# 3_3V_to_VADJ.net
KiCad netlist of a schematic drawn in Altium Designer
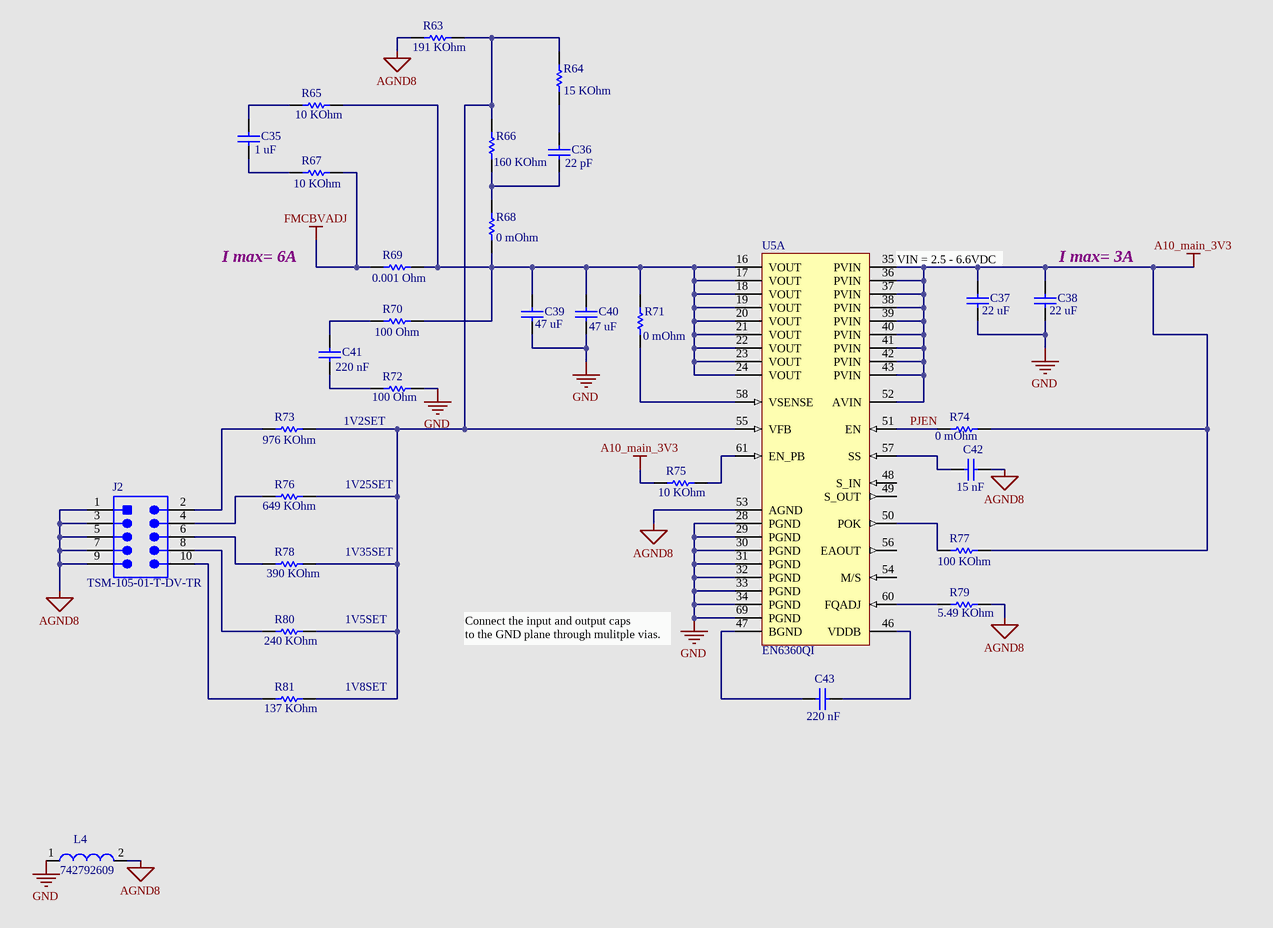
[diagram p0: 3.3V_to_VADJ.SchDoc]

(export (version "E")
  (design (tool "Eeschema 10.0.6"))
  (components
    (comp (ref "C35")
      (value "CGB2A1X5R1E105K033BC")
      (footprint "CAPC1005X33X10LL5")
      (description "Chip Capacitor, 1 uF, +/- 10%, 25 V, -55 to 85 degC, 0402 (1005 Metric), RoHS, Tape and Reel")
      (fields (field (name "TOLERANCE") "10%") (field (name "CAPACITANCE") "1 uF"))
      (libsource (lib "Altium Content Vault") (part "CAP-NP-2"))
    )
    (comp (ref "C36")
      (value "C1005C0G1H220J050BA")
      (footprint "CAPC1005X55X10LL05")
      (description "Chip Capacitor, 22 pF, +/- 5%, 50 V, -55 to 125 degC, 0402 (1005 Metric), RoHS, Tape and Reel")
      (fields (field (name "TOLERANCE") "5%") (field (name "CAPACITANCE") "22 pF"))
      (libsource (lib "") (part "CAP-NP-2_1"))
    )
    (comp (ref "C37")
      (value "GRM31CR61E226KE15L")
      (footprint "CAPC3216X180X55ML20T25")
      (description "Chip Capacitor, 22 uF, +/- 10%, 25 V, -55 to 85 degC, 1206 (3216 Metric), RoHS, Tape and Reel")
      (fields (field (name "TOLERANCE") "10%") (field (name "CAPACITANCE") "22 uF"))
      (libsource (lib "") (part "CAP-NP-2_1"))
    )
    (comp (ref "C38")
      (value "GRM31CR61E226KE15L")
      (footprint "CAPC3216X180X55ML20T25")
      (description "Chip Capacitor, 22 uF, +/- 10%, 25 V, -55 to 85 degC, 1206 (3216 Metric), RoHS, Tape and Reel")
      (fields (field (name "TOLERANCE") "10%") (field (name "CAPACITANCE") "22 uF"))
      (libsource (lib "") (part "CAP-NP-2_1"))
    )
    (comp (ref "C39")
      (value "C3216X5R1A476M160AB")
      (footprint "CAPC3216X180X20ML20")
      (description "Chip Capacitor, 47 uF, +/- 20%, 10 V, -55 to 85 degC, 1206 (3216 Metric), RoHS, Tape and Reel")
      (fields (field (name "TOLERANCE") "20%") (field (name "CAPACITANCE") "47 uF"))
      (libsource (lib "Altium Content Vault") (part "CAP-NP-2"))
    )
    (comp (ref "C40")
      (value "C3216X5R1A476M160AB")
      (footprint "CAPC3216X180X20ML20")
      (description "Chip Capacitor, 47 uF, +/- 20%, 10 V, -55 to 85 degC, 1206 (3216 Metric), RoHS, Tape and Reel")
      (fields (field (name "TOLERANCE") "20%") (field (name "CAPACITANCE") "47 uF"))
      (libsource (lib "Altium Content Vault") (part "CAP-NP-2"))
    )
    (comp (ref "C41")
      (value "GRM155R61A224KE19D")
      (footprint "CAPC1005X55X25NL05T10")
      (description "Chip Capacitor, 220 nF, +/- 10%, 10 V, -55 to 85 degC, 0402 (1005 Metric), RoHS, Tape and Reel")
      (fields
        (field (name "TOLERANCE") "10%")
        (field (name "CAPACITANCE") "220 nF")
        (field (name "MANUFACTURER") "Basic Passives")
      )
      (libsource (lib "") (part "CAP-NP-2_1"))
    )
    (comp (ref "C42")
      (value "VJ0402Y153JXQPW1BC")
      (footprint "CAPC1005X55X23ML05T8")
      (description "Chip Capacitor, 15 nF, +/- 5%, 10 V, -55 to 125 degC, 0402 (1005 Metric), RoHS, Tape and Reel")
      (fields (field (name "CAPACITANCE") "15 nF") (field (name "TOLERANCE") "5%"))
      (libsource (lib "") (part "CAP-NP-2_1"))
    )
    (comp (ref "C43")
      (value "GRM155R61A224KE19D")
      (footprint "CAPC1005X55X25NL05T10")
      (description "Chip Capacitor, 220 nF, +/- 10%, 10 V, -55 to 85 degC, 0402 (1005 Metric), RoHS, Tape and Reel")
      (fields
        (field (name "TOLERANCE") "10%")
        (field (name "CAPACITANCE") "220 nF")
        (field (name "MANUFACTURER") "Basic Passives")
      )
      (libsource (lib "") (part "CAP-NP-2_1"))
    )
    (comp (ref "J2")
      (value "TSM-105-01-T-DV-TR")
      (footprint "SMTC-TSM-105-01-T-DV_V")
      (description "Male Header, Pitch 2.54 mm, 2 x 5 Position, Height 9.65 mm, -55 to 105 degC, RoHS, Tape and Reel")
      (fields (field (name "MANUFACTURER") "Samtec"))
      (libsource (lib "Altium Content Vault") (part "CMP-1707-00003-1"))
    )
    (comp (ref "L4")
      (value "742792609")
      (footprint "SMD-0603")
      (description "SMD EMI Suppression Ferrite Bead WE-CBF, Z = 30 Ohm")
      (libsource (lib "Altium Content Vault") (part "CMP-0220-00193-1"))
    )
    (comp (ref "R63")
      (value "CRCW0402191KFKED")
      (footprint "RESC1005X40X25LL05T05")
      (description "Chip Resistor, 191 KOhm, +/- 1%, 63 mW, -55 to 155 degC, 0402 (1005 Metric), RoHS, Tape and Reel")
      (fields
        (field (name "TOLERANCE") "1%")
        (field (name "RESISTANCE") "191 KOhm")
        (field (name "MANUFACTURER") "Basic Passives")
      )
      (libsource (lib "Altium Content Vault") (part "RES-2"))
    )
    (comp (ref "R64")
      (value "ERJ-2RKF1502X")
      (footprint "RESC1005X40X25ML05T05")
      (description "Chip Resistor, 15 KOhm, +/- 1%, 100 mW, -55 to 155 degC, 0402 (1005 Metric), RoHS, Tape and Reel")
      (fields
        (field (name "RESISTANCE") "15 KOhm")
        (field (name "TOLERANCE") "1%")
        (field (name "MANUFACTURER") "Basic Passives")
      )
      (libsource (lib "Altium Content Vault") (part "RES-2"))
    )
    (comp (ref "R65")
      (value "ERJ-2RKF1002X")
      (footprint "RESC1005X40X25NL05T05")
      (description "Chip Resistor, 10 KOhm, +/- 1%, 100 mW, -55 to 155 degC, 0402 (1005 Metric), RoHS, Tape and Reel")
      (fields
        (field (name "TOLERANCE") "1%")
        (field (name "RESISTANCE") "10 KOhm")
        (field (name "MANUFACTURER") "Basic Passives")
      )
      (libsource (lib "Altium Content Vault") (part "RES-2"))
    )
    (comp (ref "R66")
      (value "CRCW0402160KFKED")
      (footprint "RESC1005X40X25ML05T05")
      (description "Chip Resistor, 160 KOhm, +/- 1%, 63 mW, -55 to 155 degC, 0402 (1005 Metric), RoHS, Tape and Reel")
      (fields
        (field (name "TOLERANCE") "1%")
        (field (name "RESISTANCE") "160 KOhm")
        (field (name "MANUFACTURER") "Basic Passives")
      )
      (libsource (lib "Altium Content Vault") (part "RES-2"))
    )
    (comp (ref "R67")
      (value "ERJ-2RKF1002X")
      (footprint "RESC1005X40X25NL05T05")
      (description "Chip Resistor, 10 KOhm, +/- 1%, 100 mW, -55 to 155 degC, 0402 (1005 Metric), RoHS, Tape and Reel")
      (fields
        (field (name "TOLERANCE") "1%")
        (field (name "RESISTANCE") "10 KOhm")
        (field (name "MANUFACTURER") "Basic Passives")
      )
      (libsource (lib "Altium Content Vault") (part "RES-2"))
    )
    (comp (ref "R68")
      (value "ERJ-2GE0R00X")
      (footprint "RESC1005X40X25ML05T05")
      (description "Chip Resistor, 0 mOhm, +/- 5%, 100 mW, -55 to 155 degC, 0402 (1005 Metric), RoHS, Tape and Reel")
      (fields
        (field (name "TOLERANCE") "5%")
        (field (name "RESISTANCE") "0 mOhm")
        (field (name "MANUFACTURER") "Basic Passives")
      )
      (libsource (lib "Altium Content Vault") (part "RES-2"))
    )
    (comp (ref "R69")
      (value "WSLP12061L000FEA")
      (footprint "RESC3216X89X104LL25T25")
      (description "Chip Resistor, 0.001 Ohm, +/- 1%, 1 W, -65 to 170 degC, 1206 (3216 Metric), RoHS, Tape and Reel")
      (fields (field (name "TOLERANCE") "1%") (field (name "RESISTANCE") "0.001 Ohm"))
      (libsource (lib "Altium Content Vault") (part "RES-2"))
    )
    (comp (ref "R70")
      (value "ERJ-2RKF1000X")
      (footprint "RESC1005X40X25LL05T05")
      (description "Chip Resistor, 100 Ohm, +/- 1%, 100 mW, -55 to 155 degC, 0402 (1005 Metric), RoHS, Tape and Reel")
      (fields
        (field (name "TOLERANCE") "1%")
        (field (name "RESISTANCE") "100 Ohm")
        (field (name "MANUFACTURER") "Basic Passives")
      )
      (libsource (lib "Altium Content Vault") (part "RES-2"))
    )
    (comp (ref "R71")
      (value "ERJ-2GE0R00X")
      (footprint "RESC1005X40X25ML05T05")
      (description "Chip Resistor, 0 mOhm, +/- 5%, 100 mW, -55 to 155 degC, 0402 (1005 Metric), RoHS, Tape and Reel")
      (fields
        (field (name "TOLERANCE") "5%")
        (field (name "RESISTANCE") "0 mOhm")
        (field (name "MANUFACTURER") "Basic Passives")
      )
      (libsource (lib "Altium Content Vault") (part "RES-2"))
    )
    (comp (ref "R72")
      (value "ERJ-2RKF1000X")
      (footprint "RESC1005X40X25LL05T05")
      (description "Chip Resistor, 100 Ohm, +/- 1%, 100 mW, -55 to 155 degC, 0402 (1005 Metric), RoHS, Tape and Reel")
      (fields
        (field (name "TOLERANCE") "1%")
        (field (name "RESISTANCE") "100 Ohm")
        (field (name "MANUFACTURER") "Basic Passives")
      )
      (libsource (lib "Altium Content Vault") (part "RES-2"))
    )
    (comp (ref "R73")
      (value "CRCW0402976KFKED")
      (footprint "RESC1005X40X25ML05T05")
      (description "Chip Resistor, 976 KOhm, +/- 1%, 63 mW, -55 to 155 degC, 0402 (1005 Metric), RoHS, Tape and Reel")
      (fields
        (field (name "RESISTANCE") "976 KOhm")
        (field (name "TOLERANCE") "1%")
        (field (name "MANUFACTURER") "Basic Passives")
      )
      (libsource (lib "Altium Content Vault") (part "RES-2"))
    )
    (comp (ref "R74")
      (value "ERJ-2GE0R00X")
      (footprint "RESC1005X40X25ML05T05")
      (description "Chip Resistor, 0 mOhm, +/- 5%, 100 mW, -55 to 155 degC, 0402 (1005 Metric), RoHS, Tape and Reel")
      (fields
        (field (name "TOLERANCE") "5%")
        (field (name "RESISTANCE") "0 mOhm")
        (field (name "MANUFACTURER") "Basic Passives")
      )
      (libsource (lib "Altium Content Vault") (part "RES-2"))
    )
    (comp (ref "R75")
      (value "ERJ-2RKF1002X")
      (footprint "RESC1005X40X25NL05T05")
      (description "Chip Resistor, 10 KOhm, +/- 1%, 100 mW, -55 to 155 degC, 0402 (1005 Metric), RoHS, Tape and Reel")
      (fields
        (field (name "TOLERANCE") "1%")
        (field (name "RESISTANCE") "10 KOhm")
        (field (name "MANUFACTURER") "Basic Passives")
      )
      (libsource (lib "Altium Content Vault") (part "RES-2"))
    )
    (comp (ref "R76")
      (value "CRCW0402649KFKED")
      (footprint "RESC1005X40X25LL05T05")
      (description "Chip Resistor, 649 KOhm, +/- 1%, 63 mW, -55 to 155 degC, 0402 (1005 Metric), RoHS, Tape and Reel")
      (fields
        (field (name "RESISTANCE") "649 KOhm")
        (field (name "TOLERANCE") "1%")
        (field (name "MANUFACTURER") "Basic Passives")
      )
      (libsource (lib "Altium Content Vault") (part "RES-2"))
    )
    (comp (ref "R77")
      (value "ERJ-2RKF1003X")
      (footprint "RESC1005X40X25LL05T05")
      (description "Chip Resistor, 100 KOhm, +/- 1%, 100 mW, -55 to 155 degC, 0402 (1005 Metric), RoHS, Tape and Reel")
      (fields
        (field (name "RESISTANCE") "100 KOhm")
        (field (name "TOLERANCE") "1%")
        (field (name "MANUFACTURER") "Basic Passives")
      )
      (libsource (lib "Altium Content Vault") (part "RES-2"))
    )
    (comp (ref "R78")
      (value "CRCW0402390KFKED")
      (footprint "RESC1005X40X25LL05T05")
      (description "Chip Resistor, 390 KOhm, +/- 1%, 63 mW, -55 to 155 degC, 0402 (1005 Metric), RoHS, Tape and Reel")
      (fields
        (field (name "RESISTANCE") "390 KOhm")
        (field (name "TOLERANCE") "1%")
        (field (name "MANUFACTURER") "Basic Passives")
      )
      (libsource (lib "Altium Content Vault") (part "RES-2"))
    )
    (comp (ref "R79")
      (value "ERJ-2RKF5491X")
      (footprint "RESC1005X40X25NL05T05")
      (description "Chip Resistor, 5.49 KOhm, +/- 1%, 100 mW, -55 to 155 degC, 0402 (1005 Metric), RoHS, Tape and Reel")
      (fields
        (field (name "TOLERANCE") "1%")
        (field (name "RESISTANCE") "5.49 KOhm")
        (field (name "MANUFACTURER") "Basic Passives")
      )
      (libsource (lib "Altium Content Vault") (part "RES-2"))
    )
    (comp (ref "R80")
      (value "ERJ-2RKF2403X")
      (footprint "RESC1005X40X25NL05T05")
      (description "Chip Resistor, 240 KOhm, +/- 1%, 100 mW, -55 to 155 degC, 0402 (1005 Metric), RoHS, Tape and Reel")
      (fields
        (field (name "RESISTANCE") "240 KOhm")
        (field (name "TOLERANCE") "1%")
        (field (name "MANUFACTURER") "Basic Passives")
      )
      (libsource (lib "Altium Content Vault") (part "RES-2"))
    )
    (comp (ref "R81")
      (value "CRCW0402137KFKED")
      (footprint "RESC1005X40X25LL05T05")
      (description "Chip Resistor, 137 KOhm, +/- 1%, 63 mW, -55 to 155 degC, 0402 (1005 Metric), RoHS, Tape and Reel")
      (fields
        (field (name "RESISTANCE") "137 KOhm")
        (field (name "TOLERANCE") "1%")
        (field (name "MANUFACTURER") "Basic Passives")
      )
      (libsource (lib "Altium Content Vault") (part "RES-2"))
    )
    (comp (ref "U5")
      (value "EN6360QI")
      (footprint "ALTR-QFN-68_A-305_V")
      (libsource (lib "Altium Content Vault") (part "ALTR-EN6360QI-QFN68"))
    )
  )
  (nets
    (net (code "1") (name "/PJEN") (class "Default")
      (node (ref "R74") (pin "1") (pinfunction "1_1") (pintype "passive"))
      (node (ref "U5") (pin "51") (pinfunction "EN_51") (pintype "input"))
    )
    (net (code "2") (name "A10_main_3V3") (class "Default")
      (node (ref "C37") (pin "2") (pinfunction "2_2") (pintype "passive"))
      (node (ref "C38") (pin "2") (pinfunction "2_2") (pintype "passive"))
      (node (ref "R74") (pin "2") (pinfunction "2_2") (pintype "passive"))
      (node (ref "R75") (pin "1") (pinfunction "1_1") (pintype "passive"))
      (node (ref "R77") (pin "2") (pinfunction "2_2") (pintype "passive"))
      (node (ref "U5") (pin "35") (pinfunction "PVIN_35") (pintype "power_in"))
      (node (ref "U5") (pin "36") (pinfunction "PVIN_36") (pintype "power_in"))
      (node (ref "U5") (pin "37") (pinfunction "PVIN_37") (pintype "power_in"))
      (node (ref "U5") (pin "38") (pinfunction "PVIN_38") (pintype "power_in"))
      (node (ref "U5") (pin "39") (pinfunction "PVIN_39") (pintype "power_in"))
      (node (ref "U5") (pin "40") (pinfunction "PVIN_40") (pintype "power_in"))
      (node (ref "U5") (pin "41") (pinfunction "PVIN_41") (pintype "power_in"))
      (node (ref "U5") (pin "42") (pinfunction "PVIN_42") (pintype "power_in"))
      (node (ref "U5") (pin "43") (pinfunction "PVIN_43") (pintype "power_in"))
      (node (ref "U5") (pin "52") (pinfunction "AVIN_52") (pintype "power_in"))
    )
    (net (code "3") (name "AGND8") (class "Default")
      (node (ref "C42") (pin "1") (pinfunction "1_1") (pintype "passive"))
      (node (ref "J2") (pin "1") (pinfunction "1_1") (pintype "passive"))
      (node (ref "J2") (pin "3") (pinfunction "3_3") (pintype "passive"))
      (node (ref "J2") (pin "5") (pinfunction "5_5") (pintype "passive"))
      (node (ref "J2") (pin "7") (pinfunction "7_7") (pintype "passive"))
      (node (ref "J2") (pin "9") (pinfunction "9_9") (pintype "passive"))
      (node (ref "L4") (pin "2") (pinfunction "2_2") (pintype "passive"))
      (node (ref "R63") (pin "1") (pinfunction "1_1") (pintype "passive"))
      (node (ref "R79") (pin "2") (pinfunction "2_2") (pintype "passive"))
      (node (ref "U5") (pin "53") (pinfunction "AGND_53") (pintype "power_in"))
    )
    (net (code "4") (name "FMCBVADJ") (class "Default")
      (node (ref "R67") (pin "2") (pinfunction "2_2") (pintype "passive"))
      (node (ref "R69") (pin "1") (pinfunction "1_1") (pintype "passive"))
    )
    (net (code "5") (name "GND") (class "Default")
      (node (ref "C37") (pin "1") (pinfunction "1_1") (pintype "passive"))
      (node (ref "C38") (pin "1") (pinfunction "1_1") (pintype "passive"))
      (node (ref "C39") (pin "1") (pinfunction "1_1") (pintype "passive"))
      (node (ref "C40") (pin "1") (pinfunction "1_1") (pintype "passive"))
      (node (ref "L4") (pin "1") (pinfunction "1_1") (pintype "passive"))
      (node (ref "R72") (pin "1") (pinfunction "1_1") (pintype "passive"))
      (node (ref "U5") (pin "28") (pinfunction "PGND_28") (pintype "power_in"))
      (node (ref "U5") (pin "29") (pinfunction "PGND_29") (pintype "power_in"))
      (node (ref "U5") (pin "30") (pinfunction "PGND_30") (pintype "power_in"))
      (node (ref "U5") (pin "31") (pinfunction "PGND_31") (pintype "power_in"))
      (node (ref "U5") (pin "32") (pinfunction "PGND_32") (pintype "power_in"))
      (node (ref "U5") (pin "33") (pinfunction "PGND_33") (pintype "power_in"))
      (node (ref "U5") (pin "34") (pinfunction "PGND_34") (pintype "power_in"))
      (node (ref "U5") (pin "69") (pinfunction "PGND_69") (pintype "power_in"))
    )
    (net (code "6") (name "Net-(C35-Pad1)") (class "Default")
      (node (ref "C35") (pin "1") (pinfunction "1_1") (pintype "passive"))
      (node (ref "R67") (pin "1") (pinfunction "1_1") (pintype "passive"))
    )
    (net (code "7") (name "Net-(C35-Pad2)") (class "Default")
      (node (ref "C35") (pin "2") (pinfunction "2_2") (pintype "passive"))
      (node (ref "R65") (pin "1") (pinfunction "1_1") (pintype "passive"))
    )
    (net (code "8") (name "Net-(C36-Pad1)") (class "Default")
      (node (ref "C36") (pin "1") (pinfunction "1_1") (pintype "passive"))
      (node (ref "R66") (pin "1") (pinfunction "1_1") (pintype "passive"))
      (node (ref "R68") (pin "2") (pinfunction "2_2") (pintype "passive"))
    )
    (net (code "9") (name "Net-(C36-Pad2)") (class "Default")
      (node (ref "C36") (pin "2") (pinfunction "2_2") (pintype "passive"))
      (node (ref "R64") (pin "1") (pinfunction "1_1") (pintype "passive"))
    )
    (net (code "10") (name "Net-(C39-Pad2)") (class "Default")
      (node (ref "C39") (pin "2") (pinfunction "2_2") (pintype "passive"))
      (node (ref "C40") (pin "2") (pinfunction "2_2") (pintype "passive"))
      (node (ref "R65") (pin "2") (pinfunction "2_2") (pintype "passive"))
      (node (ref "R68") (pin "1") (pinfunction "1_1") (pintype "passive"))
      (node (ref "R69") (pin "2") (pinfunction "2_2") (pintype "passive"))
      (node (ref "R70") (pin "1") (pinfunction "1_1") (pintype "passive"))
      (node (ref "R71") (pin "2") (pinfunction "2_2") (pintype "passive"))
      (node (ref "U5") (pin "16") (pinfunction "VOUT_16") (pintype "power_in"))
      (node (ref "U5") (pin "17") (pinfunction "VOUT_17") (pintype "power_in"))
      (node (ref "U5") (pin "18") (pinfunction "VOUT_18") (pintype "power_in"))
      (node (ref "U5") (pin "19") (pinfunction "VOUT_19") (pintype "power_in"))
      (node (ref "U5") (pin "20") (pinfunction "VOUT_20") (pintype "power_in"))
      (node (ref "U5") (pin "21") (pinfunction "VOUT_21") (pintype "power_in"))
      (node (ref "U5") (pin "22") (pinfunction "VOUT_22") (pintype "power_in"))
      (node (ref "U5") (pin "23") (pinfunction "VOUT_23") (pintype "power_in"))
      (node (ref "U5") (pin "24") (pinfunction "VOUT_24") (pintype "power_in"))
    )
    (net (code "11") (name "Net-(C41-Pad1)") (class "Default")
      (node (ref "C41") (pin "1") (pinfunction "1_1") (pintype "passive"))
      (node (ref "R70") (pin "2") (pinfunction "2_2") (pintype "passive"))
    )
    (net (code "12") (name "Net-(C41-Pad2)") (class "Default")
      (node (ref "C41") (pin "2") (pinfunction "2_2") (pintype "passive"))
      (node (ref "R72") (pin "2") (pinfunction "2_2") (pintype "passive"))
    )
    (net (code "13") (name "Net-(J2-Pad2)") (class "Default")
      (node (ref "J2") (pin "2") (pinfunction "2_2") (pintype "passive"))
      (node (ref "R73") (pin "1") (pinfunction "1_1") (pintype "passive"))
    )
    (net (code "14") (name "Net-(J2-Pad4)") (class "Default")
      (node (ref "J2") (pin "4") (pinfunction "4_4") (pintype "passive"))
      (node (ref "R76") (pin "1") (pinfunction "1_1") (pintype "passive"))
    )
    (net (code "15") (name "Net-(J2-Pad6)") (class "Default")
      (node (ref "J2") (pin "6") (pinfunction "6_6") (pintype "passive"))
      (node (ref "R78") (pin "1") (pinfunction "1_1") (pintype "passive"))
    )
    (net (code "16") (name "Net-(J2-Pad8)") (class "Default")
      (node (ref "J2") (pin "8") (pinfunction "8_8") (pintype "passive"))
      (node (ref "R80") (pin "1") (pinfunction "1_1") (pintype "passive"))
    )
    (net (code "17") (name "Net-(J2-Pad10)") (class "Default")
      (node (ref "J2") (pin "10") (pinfunction "10_10") (pintype "passive"))
      (node (ref "R81") (pin "1") (pinfunction "1_1") (pintype "passive"))
    )
    (net (code "18") (name "Net-(U5A-BGND)") (class "Default")
      (node (ref "C43") (pin "1") (pinfunction "1_1") (pintype "passive"))
      (node (ref "U5") (pin "47") (pinfunction "BGND_47") (pintype "power_in"))
    )
    (net (code "19") (name "Net-(U5A-EN_PB)") (class "Default")
      (node (ref "R75") (pin "2") (pinfunction "2_2") (pintype "passive"))
      (node (ref "U5") (pin "61") (pinfunction "EN_PB_61") (pintype "input"))
    )
    (net (code "20") (name "Net-(U5A-FQADJ)") (class "Default")
      (node (ref "R79") (pin "1") (pinfunction "1_1") (pintype "passive"))
      (node (ref "U5") (pin "60") (pinfunction "FQADJ_60") (pintype "input"))
    )
    (net (code "21") (name "Net-(U5A-POK)") (class "Default")
      (node (ref "R77") (pin "1") (pinfunction "1_1") (pintype "passive"))
      (node (ref "U5") (pin "50") (pinfunction "POK_50") (pintype "output"))
    )
    (net (code "22") (name "Net-(U5A-SS)") (class "Default")
      (node (ref "C42") (pin "2") (pinfunction "2_2") (pintype "passive"))
      (node (ref "U5") (pin "57") (pinfunction "SS_57") (pintype "input"))
    )
    (net (code "23") (name "Net-(U5A-VDDB)") (class "Default")
      (node (ref "C43") (pin "2") (pinfunction "2_2") (pintype "passive"))
      (node (ref "U5") (pin "46") (pinfunction "VDDB_46") (pintype "power_in"))
    )
    (net (code "24") (name "Net-(U5A-VFB)") (class "Default")
      (node (ref "R63") (pin "2") (pinfunction "2_2") (pintype "passive"))
      (node (ref "R64") (pin "2") (pinfunction "2_2") (pintype "passive"))
      (node (ref "R66") (pin "2") (pinfunction "2_2") (pintype "passive"))
      (node (ref "R73") (pin "2") (pinfunction "2_2") (pintype "passive"))
      (node (ref "R76") (pin "2") (pinfunction "2_2") (pintype "passive"))
      (node (ref "R78") (pin "2") (pinfunction "2_2") (pintype "passive"))
      (node (ref "R80") (pin "2") (pinfunction "2_2") (pintype "passive"))
      (node (ref "R81") (pin "2") (pinfunction "2_2") (pintype "passive"))
      (node (ref "U5") (pin "55") (pinfunction "VFB_55") (pintype "input"))
    )
    (net (code "25") (name "Net-(U5A-VSENSE)") (class "Default")
      (node (ref "R71") (pin "1") (pinfunction "1_1") (pintype "passive"))
      (node (ref "U5") (pin "58") (pinfunction "VSENSE_58") (pintype "input"))
    )
    (net (code "26") (name "unconnected-(U5A-EAOUT-Pad56)") (class "Default")
      (node (ref "U5") (pin "56") (pinfunction "EAOUT_56") (pintype "output"))
    )
    (net (code "27") (name "unconnected-(U5A-M{slash}S-Pad54)") (class "Default")
      (node (ref "U5") (pin "54") (pinfunction "M/S_54") (pintype "input"))
    )
    (net (code "28") (name "unconnected-(U5A-S_IN-Pad48)") (class "Default")
      (node (ref "U5") (pin "48") (pinfunction "S_IN_48") (pintype "input"))
    )
    (net (code "29") (name "unconnected-(U5A-S_OUT-Pad49)") (class "Default")
      (node (ref "U5") (pin "49") (pinfunction "S_OUT_49") (pintype "output"))
    )
  )
)
